# XX-Piezo-Reciever.net
KiCad netlist of a schematic drawn in EAGLE
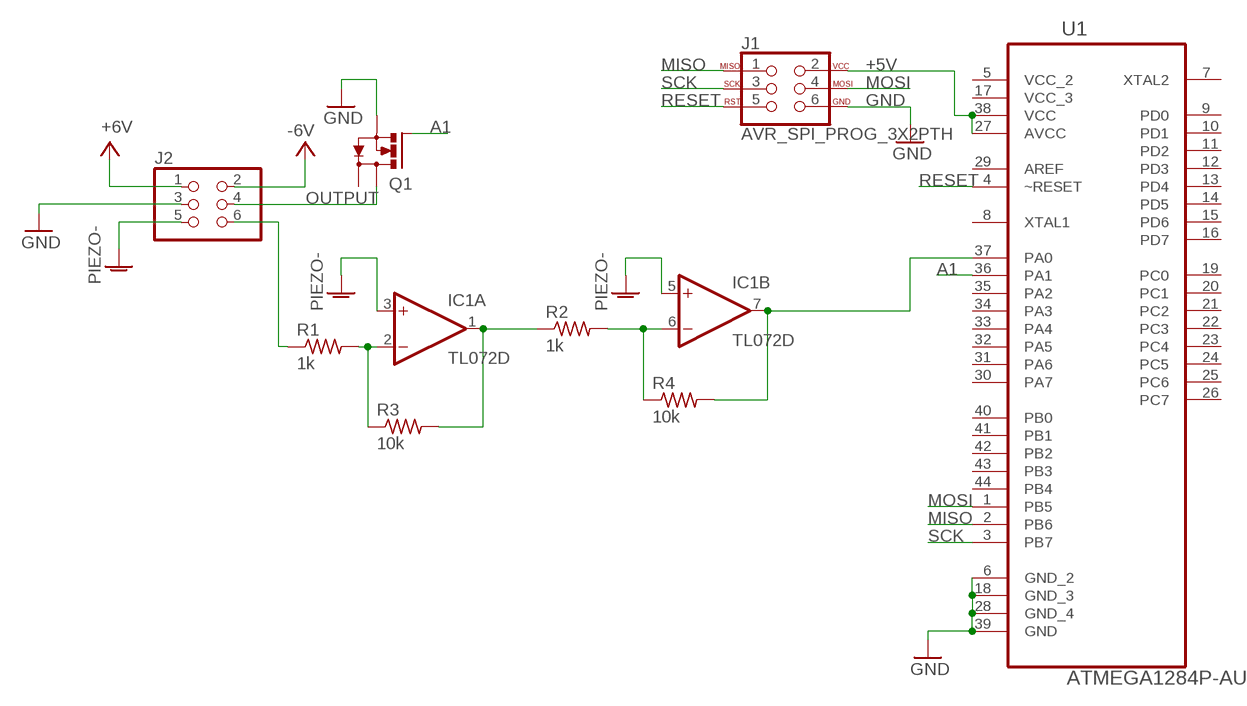
[diagram p0: schematic, sheet 1]

(export (version "E")
  (design (tool "Eeschema 10.0.6"))
  (components
    (comp (ref "IC1")
      (value "TL072D")
      (footprint "eagle-import:SO08")
      (libsource (lib "eagle-import") (part "TL072D"))
    )
    (comp (ref "J1")
      (value "AVR_SPI_PROG_3X2PTH")
      (footprint "eagle-import:2X3")
      (libsource (lib "eagle-import") (part "AVR_SPI_PROG_3X2PTH"))
    )
    (comp (ref "J2")
      (value "PINHD-2X3")
      (footprint "eagle-import:2X03")
      (libsource (lib "eagle-import") (part "PINHD-2X3"))
    )
    (comp (ref "Q1")
      (value "MOSFET_N_SOT223")
      (footprint "eagle-import:SOT223")
      (libsource (lib "eagle-import") (part "MOSFET_N_SOT223"))
    )
    (comp (ref "R1")
      (value "1k")
      (footprint "eagle-import:R0402")
      (libsource (lib "eagle-import") (part "R-US_R0402"))
    )
    (comp (ref "R2")
      (value "1k")
      (footprint "eagle-import:R0402")
      (libsource (lib "eagle-import") (part "R-US_R0402"))
    )
    (comp (ref "R3")
      (value "10k")
      (footprint "eagle-import:R0402")
      (libsource (lib "eagle-import") (part "R-US_R0402"))
    )
    (comp (ref "R4")
      (value "10k")
      (footprint "eagle-import:R0402")
      (libsource (lib "eagle-import") (part "R-US_R0402"))
    )
    (comp (ref "U1")
      (value "ATMEGA1284P-AU")
      (footprint "eagle-import:QFP80P1200X1200X120-44N")
      (libsource (lib "eagle-import") (part "ATMEGA1284P-AU"))
    )
  )
  (nets
    (net (code "1") (name "+6V") (class "Default")
      (node (ref "J2") (pin "1") (pinfunction "1_1") (pintype "passive"))
    )
    (net (code "2") (name "-6V") (class "Default")
      (node (ref "J2") (pin "2") (pinfunction "2_2") (pintype "passive"))
    )
    (net (code "3") (name "/+5V") (class "Default")
      (node (ref "J1") (pin "2") (pinfunction "2_2") (pintype "passive"))
      (node (ref "U1") (pin "27") (pinfunction "AVCC_27") (pintype "power_in"))
      (node (ref "U1") (pin "38") (pinfunction "VCC_38") (pintype "power_in"))
    )
    (net (code "4") (name "/A1") (class "Default")
      (node (ref "Q1") (pin "1") (pinfunction "G_1") (pintype "passive"))
      (node (ref "U1") (pin "36") (pinfunction "PA1_36") (pintype "bidirectional"))
    )
    (net (code "5") (name "/MISO") (class "Default")
      (node (ref "J1") (pin "1") (pinfunction "1_1") (pintype "passive"))
      (node (ref "U1") (pin "2") (pinfunction "PB6_2") (pintype "bidirectional"))
    )
    (net (code "6") (name "/MOSI") (class "Default")
      (node (ref "J1") (pin "4") (pinfunction "4_4") (pintype "passive"))
      (node (ref "U1") (pin "1") (pinfunction "PB5_1") (pintype "bidirectional"))
    )
    (net (code "7") (name "/OUTPUT") (class "Default")
      (node (ref "J2") (pin "4") (pinfunction "4_4") (pintype "passive"))
      (node (ref "Q1") (pin "2") (pinfunction "D_2") (pintype "passive"))
    )
    (net (code "8") (name "/RESET") (class "Default")
      (node (ref "J1") (pin "5") (pinfunction "5_5") (pintype "passive"))
      (node (ref "U1") (pin "4") (pinfunction "~{RESET}_4") (pintype "input"))
    )
    (net (code "9") (name "/SCK") (class "Default")
      (node (ref "J1") (pin "3") (pinfunction "3_3") (pintype "passive"))
      (node (ref "U1") (pin "3") (pinfunction "PB7_3") (pintype "bidirectional"))
    )
    (net (code "10") (name "/VCC_2") (class "Default")
      (node (ref "U1") (pin "5") (pinfunction "VCC_2_5") (pintype "power_in"))
    )
    (net (code "11") (name "/VCC_3") (class "Default")
      (node (ref "U1") (pin "17") (pinfunction "VCC_3_17") (pintype "power_in"))
    )
    (net (code "12") (name "GND") (class "Default")
      (node (ref "J1") (pin "6") (pinfunction "6_6") (pintype "passive"))
      (node (ref "J2") (pin "3") (pinfunction "3_3") (pintype "passive"))
      (node (ref "Q1") (pin "3") (pinfunction "S_3") (pintype "passive"))
      (node (ref "U1") (pin "18") (pinfunction "GND_3_18") (pintype "passive"))
      (node (ref "U1") (pin "28") (pinfunction "GND_4_28") (pintype "passive"))
      (node (ref "U1") (pin "39") (pinfunction "GND_39") (pintype "passive"))
      (node (ref "U1") (pin "6") (pinfunction "GND_2_6") (pintype "passive"))
    )
    (net (code "13") (name "Net-(IC1A--IN)") (class "Default")
      (node (ref "IC1") (pin "2") (pinfunction "-IN_2") (pintype "input"))
      (node (ref "R1") (pin "2") (pinfunction "2_2") (pintype "passive"))
      (node (ref "R3") (pin "1") (pinfunction "1_1") (pintype "passive"))
    )
    (net (code "14") (name "Net-(IC1A-OUT)") (class "Default")
      (node (ref "IC1") (pin "1") (pinfunction "OUT_1") (pintype "output"))
      (node (ref "R2") (pin "1") (pinfunction "1_1") (pintype "passive"))
      (node (ref "R3") (pin "2") (pinfunction "2_2") (pintype "passive"))
    )
    (net (code "15") (name "Net-(IC1B--IN)") (class "Default")
      (node (ref "IC1") (pin "6") (pinfunction "-IN_6") (pintype "input"))
      (node (ref "R2") (pin "2") (pinfunction "2_2") (pintype "passive"))
      (node (ref "R4") (pin "1") (pinfunction "1_1") (pintype "passive"))
    )
    (net (code "16") (name "Net-(IC1B-OUT)") (class "Default")
      (node (ref "IC1") (pin "7") (pinfunction "OUT_7") (pintype "output"))
      (node (ref "R4") (pin "2") (pinfunction "2_2") (pintype "passive"))
      (node (ref "U1") (pin "37") (pinfunction "PA0_37") (pintype "bidirectional"))
    )
    (net (code "17") (name "Net-(J2-Pad6)") (class "Default")
      (node (ref "J2") (pin "6") (pinfunction "6_6") (pintype "passive"))
      (node (ref "R1") (pin "1") (pinfunction "1_1") (pintype "passive"))
    )
    (net (code "18") (name "PIEZO-") (class "Default")
      (node (ref "IC1") (pin "3") (pinfunction "+IN_3") (pintype "input"))
      (node (ref "IC1") (pin "5") (pinfunction "+IN_5") (pintype "input"))
      (node (ref "J2") (pin "5") (pinfunction "5_5") (pintype "passive"))
    )
    (net (code "19") (name "unconnected-(Q1-D1-Pad4)") (class "Default")
      (node (ref "Q1") (pin "4") (pinfunction "D1_4") (pintype "passive"))
    )
    (net (code "20") (name "unconnected-(U1-AREF-Pad29)") (class "Default")
      (node (ref "U1") (pin "29") (pinfunction "AREF_29") (pintype "input"))
    )
    (net (code "21") (name "unconnected-(U1-PA2-Pad35)") (class "Default")
      (node (ref "U1") (pin "35") (pinfunction "PA2_35") (pintype "bidirectional"))
    )
    (net (code "22") (name "unconnected-(U1-PA3-Pad34)") (class "Default")
      (node (ref "U1") (pin "34") (pinfunction "PA3_34") (pintype "bidirectional"))
    )
    (net (code "23") (name "unconnected-(U1-PA4-Pad33)") (class "Default")
      (node (ref "U1") (pin "33") (pinfunction "PA4_33") (pintype "bidirectional"))
    )
    (net (code "24") (name "unconnected-(U1-PA5-Pad32)") (class "Default")
      (node (ref "U1") (pin "32") (pinfunction "PA5_32") (pintype "bidirectional"))
    )
    (net (code "25") (name "unconnected-(U1-PA6-Pad31)") (class "Default")
      (node (ref "U1") (pin "31") (pinfunction "PA6_31") (pintype "bidirectional"))
    )
    (net (code "26") (name "unconnected-(U1-PA7-Pad30)") (class "Default")
      (node (ref "U1") (pin "30") (pinfunction "PA7_30") (pintype "bidirectional"))
    )
    (net (code "27") (name "unconnected-(U1-PB0-Pad40)") (class "Default")
      (node (ref "U1") (pin "40") (pinfunction "PB0_40") (pintype "bidirectional"))
    )
    (net (code "28") (name "unconnected-(U1-PB1-Pad41)") (class "Default")
      (node (ref "U1") (pin "41") (pinfunction "PB1_41") (pintype "bidirectional"))
    )
    (net (code "29") (name "unconnected-(U1-PB2-Pad42)") (class "Default")
      (node (ref "U1") (pin "42") (pinfunction "PB2_42") (pintype "bidirectional"))
    )
    (net (code "30") (name "unconnected-(U1-PB3-Pad43)") (class "Default")
      (node (ref "U1") (pin "43") (pinfunction "PB3_43") (pintype "bidirectional"))
    )
    (net (code "31") (name "unconnected-(U1-PB4-Pad44)") (class "Default")
      (node (ref "U1") (pin "44") (pinfunction "PB4_44") (pintype "bidirectional"))
    )
    (net (code "32") (name "unconnected-(U1-PC0-Pad19)") (class "Default")
      (node (ref "U1") (pin "19") (pinfunction "PC0_19") (pintype "bidirectional"))
    )
    (net (code "33") (name "unconnected-(U1-PC1-Pad20)") (class "Default")
      (node (ref "U1") (pin "20") (pinfunction "PC1_20") (pintype "bidirectional"))
    )
    (net (code "34") (name "unconnected-(U1-PC2-Pad21)") (class "Default")
      (node (ref "U1") (pin "21") (pinfunction "PC2_21") (pintype "bidirectional"))
    )
    (net (code "35") (name "unconnected-(U1-PC3-Pad22)") (class "Default")
      (node (ref "U1") (pin "22") (pinfunction "PC3_22") (pintype "bidirectional"))
    )
    (net (code "36") (name "unconnected-(U1-PC4-Pad23)") (class "Default")
      (node (ref "U1") (pin "23") (pinfunction "PC4_23") (pintype "bidirectional"))
    )
    (net (code "37") (name "unconnected-(U1-PC5-Pad24)") (class "Default")
      (node (ref "U1") (pin "24") (pinfunction "PC5_24") (pintype "bidirectional"))
    )
    (net (code "38") (name "unconnected-(U1-PC6-Pad25)") (class "Default")
      (node (ref "U1") (pin "25") (pinfunction "PC6_25") (pintype "bidirectional"))
    )
    (net (code "39") (name "unconnected-(U1-PC7-Pad26)") (class "Default")
      (node (ref "U1") (pin "26") (pinfunction "PC7_26") (pintype "bidirectional"))
    )
    (net (code "40") (name "unconnected-(U1-PD0-Pad9)") (class "Default")
      (node (ref "U1") (pin "9") (pinfunction "PD0_9") (pintype "bidirectional"))
    )
    (net (code "41") (name "unconnected-(U1-PD1-Pad10)") (class "Default")
      (node (ref "U1") (pin "10") (pinfunction "PD1_10") (pintype "bidirectional"))
    )
    (net (code "42") (name "unconnected-(U1-PD2-Pad11)") (class "Default")
      (node (ref "U1") (pin "11") (pinfunction "PD2_11") (pintype "bidirectional"))
    )
    (net (code "43") (name "unconnected-(U1-PD3-Pad12)") (class "Default")
      (node (ref "U1") (pin "12") (pinfunction "PD3_12") (pintype "bidirectional"))
    )
    (net (code "44") (name "unconnected-(U1-PD4-Pad13)") (class "Default")
      (node (ref "U1") (pin "13") (pinfunction "PD4_13") (pintype "bidirectional"))
    )
    (net (code "45") (name "unconnected-(U1-PD5-Pad14)") (class "Default")
      (node (ref "U1") (pin "14") (pinfunction "PD5_14") (pintype "bidirectional"))
    )
    (net (code "46") (name "unconnected-(U1-PD6-Pad15)") (class "Default")
      (node (ref "U1") (pin "15") (pinfunction "PD6_15") (pintype "bidirectional"))
    )
    (net (code "47") (name "unconnected-(U1-PD7-Pad16)") (class "Default")
      (node (ref "U1") (pin "16") (pinfunction "PD7_16") (pintype "bidirectional"))
    )
    (net (code "48") (name "unconnected-(U1-XTAL1-Pad8)") (class "Default")
      (node (ref "U1") (pin "8") (pinfunction "XTAL1_8") (pintype "input"))
    )
    (net (code "49") (name "unconnected-(U1-XTAL2-Pad7)") (class "Default")
      (node (ref "U1") (pin "7") (pinfunction "XTAL2_7") (pintype "output"))
    )
  )
)
